# LAB-05.net
KiCad netlist of a schematic drawn in Altium Designer
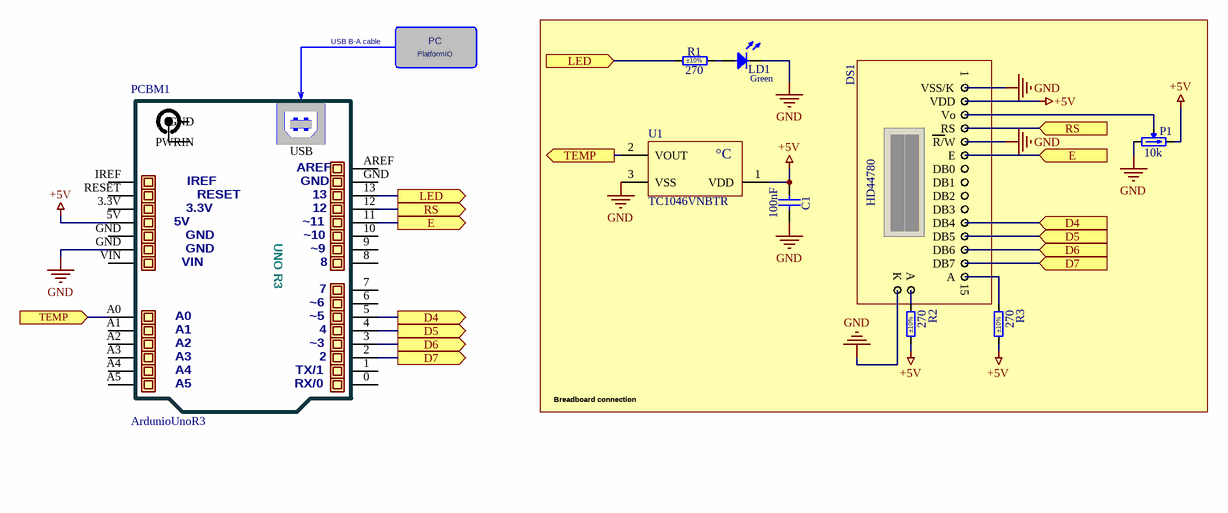
[diagram p0: LAB-05.SchDoc]

(export (version "E")
  (design (tool "Eeschema 10.0.6"))
  (components
    (comp (ref "C1")
      (value "100nF")
      (footprint "CAPC0603X33N")
      (description "Non-polarised capacitor")
      (fields
        (field (name "PART NUMBER") "CC0201_100NF_6.3V_10%_X5R")
        (field (name "VOLTAGE") "6.3V")
        (field (name "AUTHOR") "CERN DEM JLC")
      )
      (libsource (lib "Capacitors") (part "Capacitor - non polarized"))
    )
    (comp (ref "DS1")
      (value "HD44780")
      (footprint "DS_POWERTIP_PC1202LRS-AWA-B")
      (description "Alphanumeric LCD Display Module, 2 x 12 characters, Dot Size:0.45 x 0.60, Dot Pitch 0.55 x 0.70")
      (fields
        (field (name "PART NUMBER") "DS_POWERTIP_PC1202LRS-AWA-B")
        (field (name "MANUFACTURER") "POWERTIP")
        (field (name "AUTHOR") "CERN DEM JLC")
      )
      (libsource (lib "ICs And Semiconductors") (part "DS_POWERTIP_PC1202"))
    )
    (comp (ref "LD1")
      (value "Green")
      (footprint "LED_DIALIGHT_561-2201-050F")
      (description "LED Green 1C 2A")
      (fields
        (field (name "PART NUMBER") "LED_DIALIGHT_561-2201-050F")
        (field (name "MANUFACTURER") "DIALIGHT")
        (field (name "AUTHOR") "CERN DEM JLC")
      )
      (libsource (lib "ICs And Semiconductors") (part "LED Green 1C 2A"))
    )
    (comp (ref "P1")
      (value "10k")
      (footprint "TRIM_BOURNS_3314G-1")
      (description "Trimming Potentiometer")
      (fields
        (field (name "PART NUMBER") "TRIM_1T_10K_BOURNS_3314G-1-103E")
        (field (name "POWER") "0.25W")
        (field (name "AUTHOR") "CERN DEM JLC")
      )
      (libsource (lib "Resistors") (part "Trimming Potentiometer"))
    )
    (comp (ref "PCBM1")
      (value "ArdunioUnoR3")
      (description "ArdunioUnoR3 Universal SCH Symbol \r\n(C) 230232")
      (libsource (lib "ArduinoUnoR3") (part "ArdunioUnoR3"))
    )
    (comp (ref "R1")
      (value "270")
      (footprint "RESC3216X65N")
      (description "Resistor - 0.1%")
      (fields
        (field (name "TOLERANCE") "±10%")
        (field (name "PART NUMBER") "R1206_270R_0.1%_0.25W_25PPM")
        (field (name "POWER") "0.25W")
        (field (name "AUTHOR") "CERN DEM JLC")
      )
      (libsource (lib "Resistors") (part "Resistor - 0.1%"))
    )
    (comp (ref "R2")
      (value "270")
      (footprint "RESC3216X65N")
      (description "Resistor - 0.1%")
      (fields
        (field (name "TOLERANCE") "±10%")
        (field (name "PART NUMBER") "R1206_270R_0.1%_0.25W_25PPM")
        (field (name "POWER") "0.25W")
        (field (name "AUTHOR") "CERN DEM JLC")
      )
      (libsource (lib "Resistors") (part "Resistor - 0.1%"))
    )
    (comp (ref "R3")
      (value "270")
      (footprint "RESC3216X65N")
      (description "Resistor - 0.1%")
      (fields
        (field (name "TOLERANCE") "±10%")
        (field (name "PART NUMBER") "R1206_270R_0.1%_0.25W_25PPM")
        (field (name "POWER") "0.25W")
        (field (name "AUTHOR") "CERN DEM JLC")
      )
      (libsource (lib "Resistors") (part "Resistor - 0.1%"))
    )
    (comp (ref "U1")
      (value "TC1046VNBTR")
      (footprint "SOT-23-NB3_L")
      (description "High Precision Temperature-to-Voltage Converter, 3-Pin SOT-23, Extended Temperature, Tape and Reel")
      (libsource (lib "Altium Content Vault") (part "CON-TVC-TC1046-3"))
    )
  )
  (nets
    (net (code "1") (name "+5V") (class "Default")
      (node (ref "C1") (pin "2") (pinfunction "2_2") (pintype "passive"))
      (node (ref "P1") (pin "3") (pinfunction "CW_3") (pintype "passive"))
      (node (ref "PCBM1") (pin "5V") (pinfunction "5V_5V") (pintype "passive"))
      (node (ref "R2") (pin "2") (pinfunction "2_2") (pintype "passive"))
      (node (ref "R3") (pin "2") (pinfunction "2_2") (pintype "passive"))
      (node (ref "U1") (pin "1") (pinfunction "VDD_1") (pintype "power_in"))
    )
    (net (code "2") (name "/D4") (class "Default")
      (node (ref "PCBM1") (pin "5") (pinfunction "5_5") (pintype "passive"))
    )
    (net (code "3") (name "/D5") (class "Default")
      (node (ref "PCBM1") (pin "4") (pinfunction "4_4") (pintype "passive"))
    )
    (net (code "4") (name "/D6") (class "Default")
      (node (ref "PCBM1") (pin "3") (pinfunction "3_3") (pintype "passive"))
    )
    (net (code "5") (name "/D7") (class "Default")
      (node (ref "PCBM1") (pin "2") (pinfunction "2_2") (pintype "passive"))
    )
    (net (code "6") (name "/E") (class "Default")
      (node (ref "PCBM1") (pin "11") (pinfunction "11_11") (pintype "passive"))
    )
    (net (code "7") (name "/LED") (class "Default")
      (node (ref "PCBM1") (pin "13") (pinfunction "13_13") (pintype "passive"))
      (node (ref "R1") (pin "1") (pinfunction "1_1") (pintype "passive"))
    )
    (net (code "8") (name "/RS") (class "Default")
      (node (ref "PCBM1") (pin "12") (pinfunction "12_12") (pintype "passive"))
    )
    (net (code "9") (name "/TEMP") (class "Default")
      (node (ref "PCBM1") (pin "A0") (pinfunction "A0_A0") (pintype "passive"))
      (node (ref "U1") (pin "2") (pinfunction "VOUT_2") (pintype "power_in"))
    )
    (net (code "10") (name "GND") (class "Default")
      (node (ref "C1") (pin "1") (pinfunction "1_1") (pintype "passive"))
      (node (ref "LD1") (pin "1") (pinfunction "C_1") (pintype "passive"))
      (node (ref "P1") (pin "1") (pinfunction "CCW_1") (pintype "passive"))
      (node (ref "PCBM1") (pin "GND") (pinfunction "GND_GND") (pintype "passive"))
      (node (ref "U1") (pin "3") (pinfunction "VSS_3") (pintype "power_in"))
    )
    (net (code "11") (name "Net-(LD1-A)") (class "Default")
      (node (ref "LD1") (pin "2") (pinfunction "A_2") (pintype "passive"))
      (node (ref "R1") (pin "2") (pinfunction "2_2") (pintype "passive"))
    )
    (net (code "12") (name "unconnected-(P1-W-Pad2)") (class "Default")
      (node (ref "P1") (pin "2") (pinfunction "W_2") (pintype "passive"))
    )
    (net (code "13") (name "unconnected-(PCBM1-Pad0)") (class "Default")
      (node (ref "PCBM1") (pin "0") (pinfunction "0_0") (pintype "passive"))
    )
    (net (code "14") (name "unconnected-(PCBM1-Pad1)") (class "Default")
      (node (ref "PCBM1") (pin "1") (pinfunction "1_1") (pintype "passive"))
    )
    (net (code "15") (name "unconnected-(PCBM1-Pad3.3V)") (class "Default")
      (node (ref "PCBM1") (pin "3.3V") (pinfunction "3.3V_3.3V") (pintype "passive"))
    )
    (net (code "16") (name "unconnected-(PCBM1-Pad6)") (class "Default")
      (node (ref "PCBM1") (pin "6") (pinfunction "6_6") (pintype "passive"))
    )
    (net (code "17") (name "unconnected-(PCBM1-Pad7)") (class "Default")
      (node (ref "PCBM1") (pin "7") (pinfunction "7_7") (pintype "passive"))
    )
    (net (code "18") (name "unconnected-(PCBM1-Pad8)") (class "Default")
      (node (ref "PCBM1") (pin "8") (pinfunction "8_8") (pintype "passive"))
    )
    (net (code "19") (name "unconnected-(PCBM1-Pad9)") (class "Default")
      (node (ref "PCBM1") (pin "9") (pinfunction "9_9") (pintype "passive"))
    )
    (net (code "20") (name "unconnected-(PCBM1-Pad10)") (class "Default")
      (node (ref "PCBM1") (pin "10") (pinfunction "10_10") (pintype "passive"))
    )
    (net (code "21") (name "unconnected-(PCBM1-PadA1)") (class "Default")
      (node (ref "PCBM1") (pin "A1") (pinfunction "A1_A1") (pintype "passive"))
    )
    (net (code "22") (name "unconnected-(PCBM1-PadA2)") (class "Default")
      (node (ref "PCBM1") (pin "A2") (pinfunction "A2_A2") (pintype "passive"))
    )
    (net (code "23") (name "unconnected-(PCBM1-PadA3)") (class "Default")
      (node (ref "PCBM1") (pin "A3") (pinfunction "A3_A3") (pintype "passive"))
    )
    (net (code "24") (name "unconnected-(PCBM1-PadA4)") (class "Default")
      (node (ref "PCBM1") (pin "A4") (pinfunction "A4_A4") (pintype "passive"))
    )
    (net (code "25") (name "unconnected-(PCBM1-PadA5)") (class "Default")
      (node (ref "PCBM1") (pin "A5") (pinfunction "A5_A5") (pintype "passive"))
    )
    (net (code "26") (name "unconnected-(PCBM1-PadAREF)") (class "Default")
      (node (ref "PCBM1") (pin "AREF") (pinfunction "AREF_AREF") (pintype "passive"))
    )
    (net (code "27") (name "unconnected-(PCBM1-PadGND)") (class "Default")
      (node (ref "PCBM1") (pin "GND") (pinfunction "GND_GND") (pintype "passive"))
    )
    (net (code "28") (name "unconnected-(PCBM1-PadGND)_1") (class "Default")
      (node (ref "PCBM1") (pin "GND") (pinfunction "GND_GND") (pintype "passive"))
    )
    (net (code "29") (name "unconnected-(PCBM1-PadIREF)") (class "Default")
      (node (ref "PCBM1") (pin "IREF") (pinfunction "IREF_IREF") (pintype "passive"))
    )
    (net (code "30") (name "unconnected-(PCBM1-PadRESET)") (class "Default")
      (node (ref "PCBM1") (pin "RESET") (pinfunction "RESET_RESET") (pintype "passive"))
    )
    (net (code "31") (name "unconnected-(PCBM1-PadVIN)") (class "Default")
      (node (ref "PCBM1") (pin "VIN") (pinfunction "VIN_VIN") (pintype "passive"))
    )
    (net (code "32") (name "unconnected-(R2-Pad1)") (class "Default")
      (node (ref "R2") (pin "1") (pinfunction "1_1") (pintype "passive"))
    )
    (net (code "33") (name "unconnected-(R3-Pad1)") (class "Default")
      (node (ref "R3") (pin "1") (pinfunction "1_1") (pintype "passive"))
    )
  )
)
